# SENSOR.net
KiCad netlist of a schematic drawn in Altium Designer
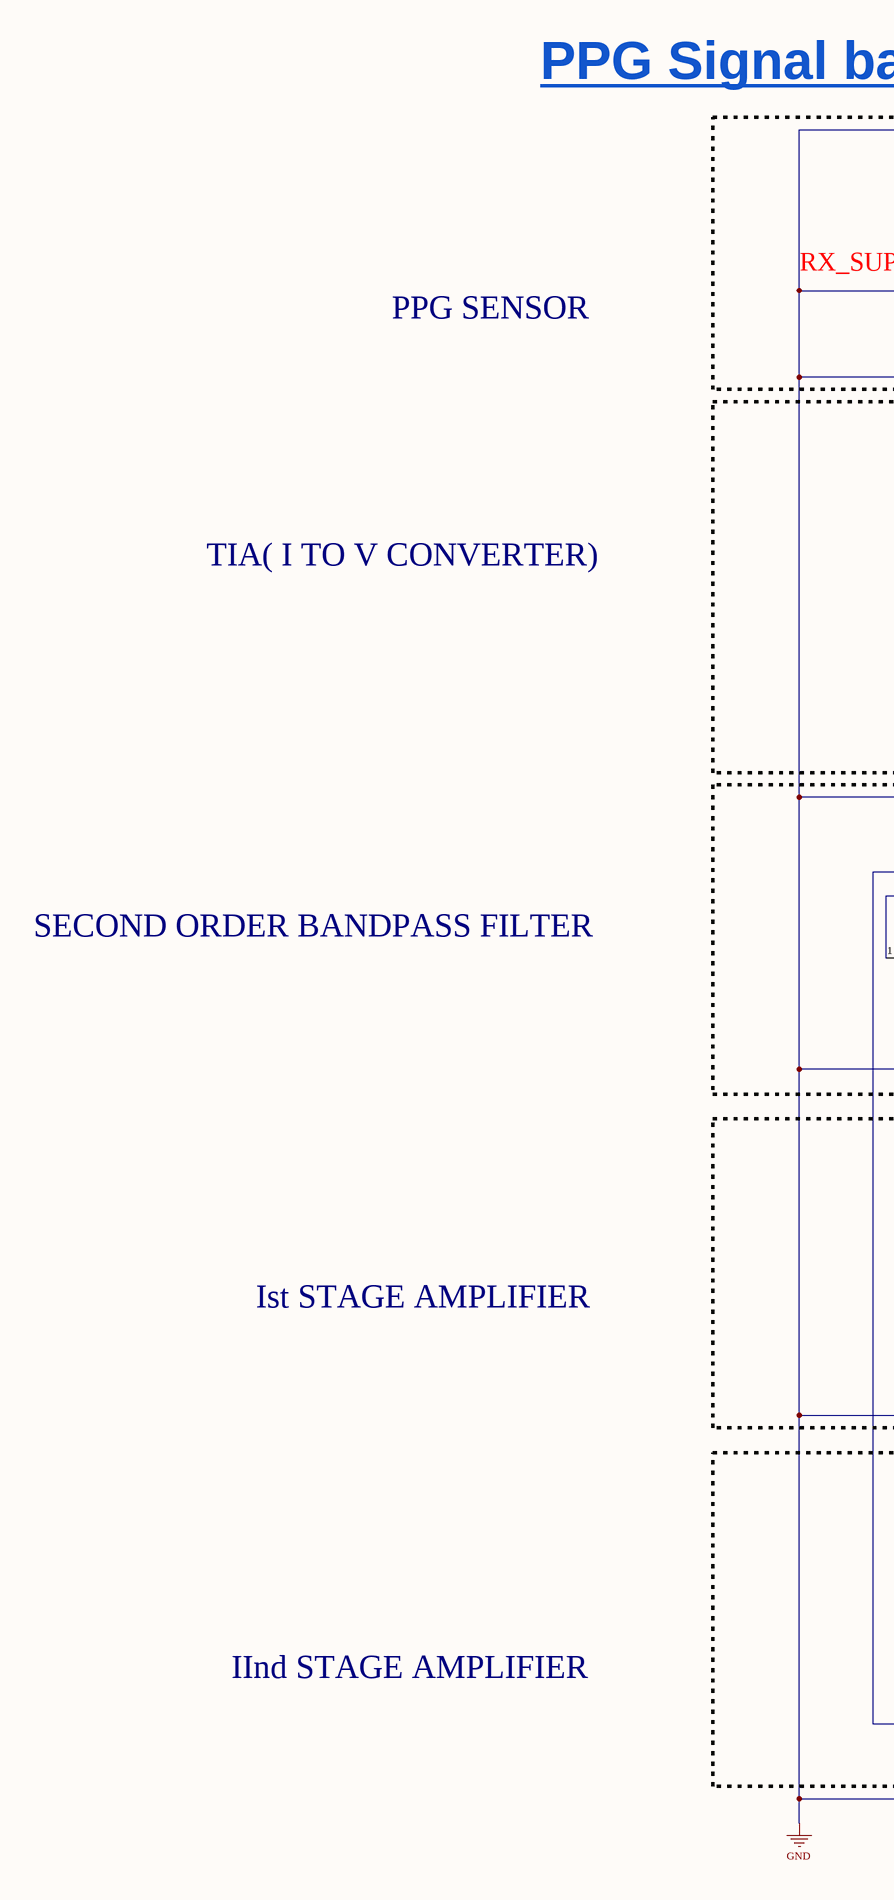
[diagram p0: SENSOR.SchDoc, left]
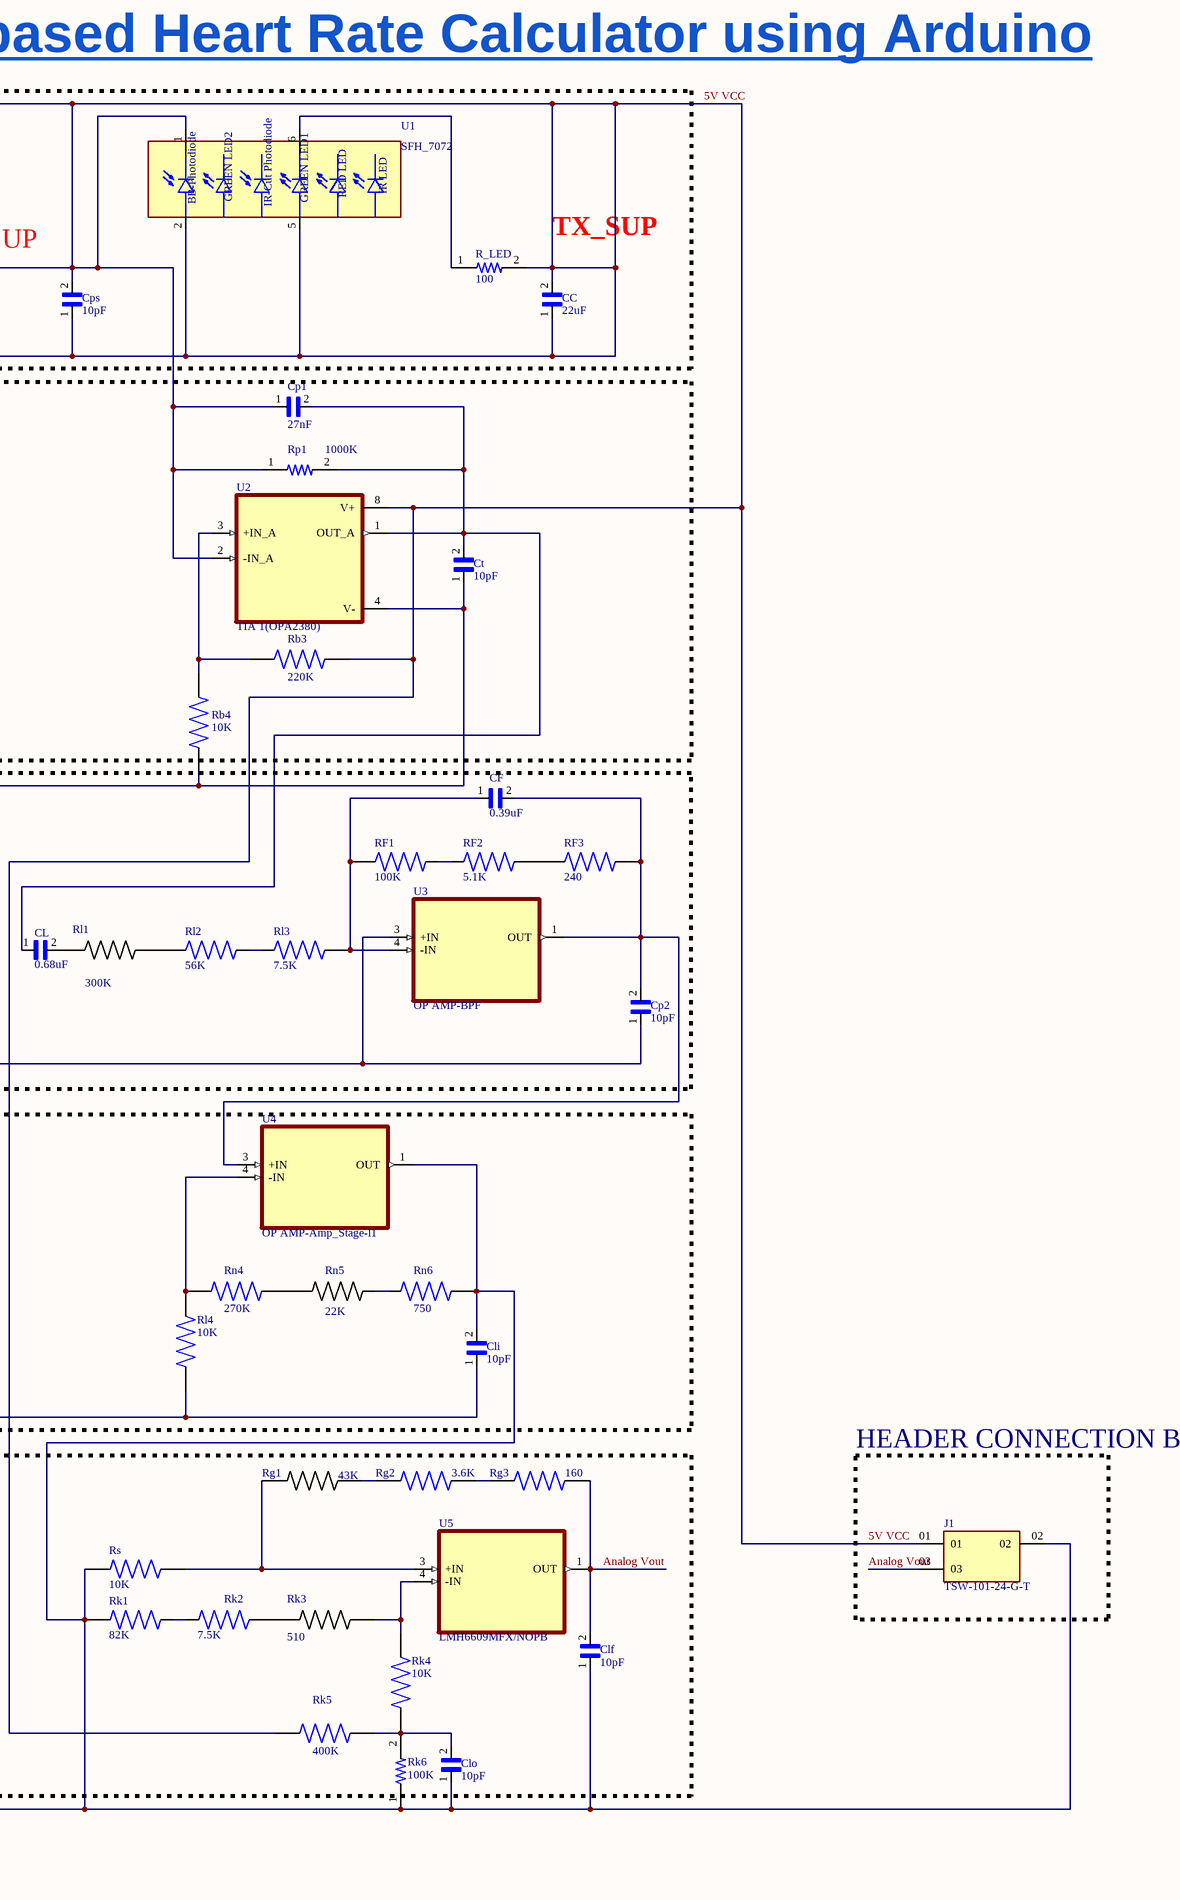
[diagram p1: SENSOR.SchDoc, right]

(export (version "E")
  (design (tool "Eeschema 10.0.6"))
  (components
    (comp (ref "CC")
      (value "22uF")
      (footprint "INDC2112X145N")
      (description "22ÂµF Â±20% 10V Ceramic Capacitor X5R 0805 (2012 Metric)")
      (fields (field (name "MF") "Taiyo Yuden") (field (name "MP") "LMK212BBJ226MG-T"))
      (libsource (lib "LMK212BBJ226MG-T") (part "LMK212BBJ226MG-T"))
    )
    (comp (ref "CF")
      (value "0.39uF")
      (footprint "CAPC2012X140N")
      (description "0.39ÂµF Â±5% 16V Ceramic Capacitor X7R 0805 _2012 Metric_")
      (fields (field (name "MF") "AVX") (field (name "DIGI-KEY_PART_NUMBER") "478-10574-2-ND"))
      (libsource (lib "0805YC394JAT2A") (part "0805YC394JAT2A"))
    )
    (comp (ref "CL")
      (value "0.68uF")
      (footprint "CAPC1608X90N")
      (description "Multilayer Ceramic Capacitor, C Series, 0.68 - F, - 10%, X7R, 16 V, 0603 [1608 Metric]")
      (fields (field (name "MP") "C1608X7R1C684K080AC"))
      (libsource (lib "C1608X7R1C684K080AC") (part "C1608X7R1C684K080AC"))
    )
    (comp (ref "Clf")
      (value "10pF")
      (footprint "CAPC1608X90N")
      (description "10PF 5% 50V C0G 0603")
      (fields (field (name "MP") "06035A100JAT2A"))
      (libsource (lib "06035A100JAT2A") (part "06035A100JAT2A"))
    )
    (comp (ref "Cli")
      (value "10pF")
      (footprint "CAPC1608X90N")
      (description "10PF 5% 50V C0G 0603")
      (fields (field (name "MP") "06035A100JAT2A"))
      (libsource (lib "06035A100JAT2A") (part "06035A100JAT2A"))
    )
    (comp (ref "Clo")
      (value "10pF")
      (footprint "CAPC1608X90N")
      (description "10PF 5% 50V C0G 0603")
      (fields (field (name "MP") "06035A100JAT2A"))
      (libsource (lib "06035A100JAT2A") (part "06035A100JAT2A"))
    )
    (comp (ref "Cp1")
      (value "27nF")
      (footprint "CAPC5750X330N")
      (description "2220GC273KAT1A")
      (fields (field (name "MF") "AVX") (field (name "DIGI-KEY_PART_NUMBER") "478-7018-1-ND"))
      (libsource (lib "06033C104KAT4A") (part "06033C104KAT4A"))
    )
    (comp (ref "Cp2")
      (value "10pF")
      (footprint "CAPC1608X90N")
      (description "10PF 5% 50V C0G 0603")
      (fields (field (name "MP") "06035A100JAT2A"))
      (libsource (lib "06035A100JAT2A") (part "06035A100JAT2A"))
    )
    (comp (ref "Cps")
      (value "10pF")
      (footprint "CAPC1608X90N")
      (description "10PF 5% 50V C0G 0603")
      (fields (field (name "MP") "06035A100JAT2A"))
      (libsource (lib "06035A100JAT2A") (part "06035A100JAT2A"))
    )
    (comp (ref "Ct")
      (value "10pF")
      (footprint "CAPC1608X90N")
      (description "10PF 5% 50V C0G 0603")
      (fields (field (name "MP") "06035A100JAT2A"))
      (libsource (lib "06035A100JAT2A") (part "06035A100JAT2A"))
    )
    (comp (ref "J1")
      (value "TSW-101-24-G-T")
      (footprint "SAMTEC_TSW-101-24-G-T")
      (description "Connector Header Through Hole 3 position")
      (fields (field (name "MF") "Samtec"))
      (libsource (lib "TSW-101-24-G-T") (part "TSW-101-24-G-T"))
    )
    (comp (ref "Rb3")
      (value "220K")
      (footprint "RESC1005X40N")
      (description "Fixed Resistor CRGCQ 0402 220K 1%")
      (fields (field (name "MP") "CRGCQ0402F220K"))
      (libsource (lib "CRGCQ0402F220K") (part "CRGCQ0402F220K"))
    )
    (comp (ref "Rb4")
      (value "10K")
      (footprint "RESC0603X26N")
      (description "10 kOhms Â±1% 0.05W, 1/20W Chip Resistor 0201 (0603 Metric) Thick Film")
      (fields (field (name "MP") "RMCF0201FT10K0") (field (name "MF") "Stackpole Electronics Inc"))
      (libsource (lib "RMCF0201FT10K0") (part "RMCF0201FT10K0"))
    )
    (comp (ref "RF1")
      (value "100K")
      (footprint "RESC1005X40N")
      (description "RES, THIN FILM, 100K, 0.5%, 0.063W, 0402, REEL")
      (fields (field (name "MP") "RR0510P-104-D"))
      (libsource (lib "RR0510P-104-D") (part "RR0510P-104-D"))
    )
    (comp (ref "RF2")
      (value "5.1K")
      (footprint "RES_ERA3AEB512V")
      (description "5.1 kOhms 0.1% 0.1W, 1/10W Chip Resistor 0603 (1608 Metric) Automotive AEC-Q200 Thin Film")
      (fields (field (name "MF") "Panasonic") (field (name "MP") "ERA-3AEB512V"))
      (libsource (lib "ERA3AEB512V") (part "ERA3AEB512V"))
    )
    (comp (ref "RF3")
      (value "240")
      (footprint "RES_ERA2AED241X")
      (description "240 Ohms 0.5% 0.063W, 1/16W Chip Resistor 0402 (1005 Metric) Automotive AEC-Q200 Thin Film")
      (fields (field (name "MF") "Panasonic") (field (name "MP") "ERA-2AED241X"))
      (libsource (lib "ERA2AED241X") (part "ERA2AED241X"))
    )
    (comp (ref "Rg1")
      (value "43K")
      (footprint "*RES_ERJ1GNF4302C")
      (description "None")
      (fields (field (name "MP") "ERJ1GNF4302C") (field (name "MF") "Panasonic"))
      (libsource (lib "ERJ1GNF4302C") (part "ERJ1GNF4302C"))
    )
    (comp (ref "Rg2")
      (value "3.6K")
      (footprint "RESC1005X35N")
      (fields (field (name "MP") "RMCF0402FT3K60"))
      (libsource (lib "RMCF0402FT3K60") (part "RMCF0402FT3K60"))
    )
    (comp (ref "Rg3")
      (value "160")
      (footprint "RESC0603X26N")
      (description "Res Thick Film 0201 160 Ohm 1% 0.05W(1/20W) Â±200ppm/Â°C Pad SMD T/R")
      (fields (field (name "MP") "RC0201FR-07160RL") (field (name "MF") "Yageo"))
      (libsource (lib "RC0201FR-07160RL") (part "RC0201FR-07160RL"))
    )
    (comp (ref "Rk1")
      (value "82K")
      (footprint "RESC1005X40N")
      (description "Fixed Resistor CRGCQ 0402 82K 1%")
      (fields (field (name "MP") "CRGCQ0402F82K"))
      (libsource (lib "CRGCQ0402F82K") (part "CRGCQ0402F82K"))
    )
    (comp (ref "Rk2")
      (value "7.5K")
      (footprint "RESC1508X50N")
      (fields (field (name "MP") "RNCP0603FTD7K50"))
      (libsource (lib "RNCP0603FTD7K50") (part "RNCP0603FTD7K50"))
    )
    (comp (ref "Rk3")
      (value "510")
      (footprint "*RESC0603X26N")
      (libsource (lib "RC0201FR-07510RL") (part "RC0201FR-07510RL"))
    )
    (comp (ref "Rk4")
      (value "10K")
      (footprint "RESC0603X26N")
      (description "10 kOhms Â±1% 0.05W, 1/20W Chip Resistor 0201 (0603 Metric) Thick Film")
      (fields (field (name "MP") "RMCF0201FT10K0") (field (name "MF") "Stackpole Electronics Inc"))
      (libsource (lib "RMCF0201FT10K0") (part "RMCF0201FT10K0"))
    )
    (comp (ref "Rk5")
      (value "400K")
      (footprint "RESC2012X50N")
      (fields (field (name "MP") "CRCW0805400KJNTA"))
      (libsource (lib "CRCW0805400KJNTA") (part "CRCW0805400KJNTA"))
    )
    (comp (ref "Rk6")
      (value "100K")
      (footprint "RESC0603X26N")
      (description "100 kOhms Â±5% 0.05W, 1/20W Chip Resistor 0201 _0603 Metric_ Moisture Resistant Thick Film")
      (fields (field (name "DIGI-KEY_PART_NUMBER") "311-100KNCT-ND") (field (name "MF") "Yageo"))
      (libsource (lib "RC0201JR-07100KL") (part "RC0201JR-07100KL"))
    )
    (comp (ref "Rl1")
      (value "300K")
      (footprint "*RES_ERA3AEB304V")
      (libsource (lib "ERA3AEB304V") (part "ERA3AEB304V"))
    )
    (comp (ref "Rl2")
      (value "56K")
      (footprint "RESC1005X40N")
      (description "Fixed Resistor CRGCQ 0402 56K 1%")
      (fields (field (name "MP") "CRGCQ0402F56K"))
      (libsource (lib "CRGCQ0402F56K") (part "CRGCQ0402F56K"))
    )
    (comp (ref "Rl3")
      (value "7.5K")
      (footprint "RESC1508X50N")
      (fields (field (name "MP") "RNCP0603FTD7K50"))
      (libsource (lib "RNCP0603FTD7K50") (part "RNCP0603FTD7K50"))
    )
    (comp (ref "Rl4")
      (value "10K")
      (footprint "RESC0603X26N")
      (description "10 kOhms Â±1% 0.05W, 1/20W Chip Resistor 0201 (0603 Metric) Thick Film")
      (fields (field (name "MP") "RMCF0201FT10K0") (field (name "MF") "Stackpole Electronics Inc"))
      (libsource (lib "RMCF0201FT10K0") (part "RMCF0201FT10K0"))
    )
    (comp (ref "Rn4")
      (value "270K")
      (footprint "RESC2012X65N")
      (description "CRG0805 1% 270K")
      (fields (field (name "MP") "CRG0805F270K"))
      (libsource (lib "CRG0805F270K") (part "CRG0805F270K"))
    )
    (comp (ref "Rn5")
      (value "22K")
      (footprint "*RES_ERA2AEB223X")
      (libsource (lib "ERA2AEB223X") (part "ERA2AEB223X"))
    )
    (comp (ref "Rn6")
      (value "750")
      (footprint "RES_ERA3AEB751V")
      (description "750 Ohms 0.1% 0.1W, 1/10W Chip Resistor 0603 (1608 Metric) Automotive AEC-Q200 Thin Film")
      (fields (field (name "MP") "ERA-3AEB751V") (field (name "MF") "Panasonic"))
      (libsource (lib "ERA3AEB751V") (part "ERA3AEB751V"))
    )
    (comp (ref "Rp1")
      (value "1000K")
      (footprint "RESC0603X26N")
      (description "1 MOhms Â±1% 0.05W, 1/20W Chip Resistor 0201 (0603 Metric) Moisture Resistant Thick Film")
      (fields (field (name "MP") "RC0201FR-071ML") (field (name "MF") "Yageo"))
      (libsource (lib "RC0201FR-071ML") (part "RC0201FR-071ML"))
    )
    (comp (ref "Rs")
      (value "10K")
      (footprint "RESC0603X26N")
      (description "10 kOhms Â±1% 0.05W, 1/20W Chip Resistor 0201 (0603 Metric) Thick Film")
      (fields (field (name "MP") "RMCF0201FT10K0") (field (name "MF") "Stackpole Electronics Inc"))
      (libsource (lib "RMCF0201FT10K0") (part "RMCF0201FT10K0"))
    )
    (comp (ref "R_LED")
      (value "100")
      (footprint "RESC0603X26N")
      (description "100 Ohms Â±1% 0.05W, 1/20W Chip Resistor 0201 _0603 Metric_ Moisture Resistant Thick Film")
      (fields (field (name "MF") "Yageo") (field (name "MP") "RC0201FR-07100RL"))
      (libsource (lib "RC0201FR-07100RL") (part "RC0201FR-07100RL"))
    )
    (comp (ref "U1")
      (value "SFH_7072")
      (footprint "XDCR_SFH_7072")
      (description "Reflective Optical Sensor 6-SMD, No Lead")
      (fields (field (name "MP") "SFH 7072") (field (name "MF") "OSRAM Opto"))
      (libsource (lib "SFH_7072") (part "SFH_7072"))
    )
    (comp (ref "U2")
      (value "TIA 1(OPA2380)")
      (footprint "SOP65P490X110-8N")
      (fields (field (name "MP") "OPA2380AIDGKT"))
      (libsource (lib "OPA2380AIDGKT") (part "OPA2380AIDGKT"))
    )
    (comp (ref "U3")
      (value "OP AMP-BPF")
      (footprint "SOT95P280X145-5N")
      (fields (field (name "MP") "LMH6609MFX/NOPB"))
      (libsource (lib "LMH6609MFX_NOPB") (part "LMH6609MFX/NOPB"))
    )
    (comp (ref "U4")
      (value "OP AMP-Amp_Stage-l1")
      (footprint "SOT95P280X145-5N")
      (fields (field (name "MP") "LMH6609MFX/NOPB"))
      (libsource (lib "LMH6609MFX_NOPB") (part "LMH6609MFX/NOPB"))
    )
    (comp (ref "U5")
      (value "LMH6609MFX/NOPB")
      (footprint "SOT95P280X145-5N")
      (libsource (lib "LMH6609MFX_NOPB") (part "LMH6609MFX/NOPB"))
    )
  )
  (nets
    (net (code "1") (name "/Analog Vout") (class "Default")
      (node (ref "Clf") (pin "2") (pinfunction "2_2") (pintype "passive"))
      (node (ref "J1") (pin "03") (pinfunction "03_03") (pintype "passive"))
      (node (ref "Rg3") (pin "2") (pinfunction "2_2") (pintype "passive"))
      (node (ref "U5") (pin "1") (pinfunction "OUT_1") (pintype "output"))
    )
    (net (code "2") (name "GND") (class "Default")
      (node (ref "CC") (pin "1") (pinfunction "1_1") (pintype "passive"))
      (node (ref "CC") (pin "2") (pinfunction "2_2") (pintype "passive"))
      (node (ref "Clf") (pin "1") (pinfunction "1_1") (pintype "passive"))
      (node (ref "Cli") (pin "1") (pinfunction "1_1") (pintype "passive"))
      (node (ref "Cli") (pin "2") (pinfunction "2_2") (pintype "passive"))
      (node (ref "Clo") (pin "1") (pinfunction "1_1") (pintype "passive"))
      (node (ref "Cp1") (pin "1") (pinfunction "1_1") (pintype "passive"))
      (node (ref "Cp2") (pin "1") (pinfunction "1_1") (pintype "passive"))
      (node (ref "Cps") (pin "1") (pinfunction "1_1") (pintype "passive"))
      (node (ref "Cps") (pin "2") (pinfunction "2_2") (pintype "passive"))
      (node (ref "Ct") (pin "1") (pinfunction "1_1") (pintype "passive"))
      (node (ref "J1") (pin "01") (pinfunction "01_01") (pintype "passive"))
      (node (ref "J1") (pin "02") (pinfunction "02_02") (pintype "passive"))
      (node (ref "R_LED") (pin "2") (pinfunction "2_2") (pintype "passive"))
      (node (ref "Rb3") (pin "2") (pinfunction "2_2") (pintype "passive"))
      (node (ref "Rb4") (pin "1") (pinfunction "1_1") (pintype "passive"))
      (node (ref "Rk1") (pin "1") (pinfunction "1_1") (pintype "passive"))
      (node (ref "Rk5") (pin "1") (pinfunction "1_1") (pintype "passive"))
      (node (ref "Rk6") (pin "1") (pinfunction "1_1") (pintype "passive"))
      (node (ref "Rl4") (pin "1") (pinfunction "1_1") (pintype "passive"))
      (node (ref "Rn6") (pin "2") (pinfunction "2_2") (pintype "passive"))
      (node (ref "Rp1") (pin "1") (pinfunction "1_1") (pintype "passive"))
      (node (ref "Rs") (pin "1") (pinfunction "1_1") (pintype "passive"))
      (node (ref "U1") (pin "1") (pinfunction "BPC_1") (pintype "passive"))
      (node (ref "U1") (pin "2") (pinfunction "BPA_2") (pintype "passive"))
      (node (ref "U1") (pin "5") (pinfunction "G1A_5") (pintype "passive"))
      (node (ref "U2") (pin "2") (pinfunction "-IN_A_2") (pintype "input"))
      (node (ref "U2") (pin "4") (pinfunction "V-_4") (pintype "power_in"))
      (node (ref "U2") (pin "8") (pinfunction "V+_8") (pintype "power_in"))
      (node (ref "U3") (pin "3") (pinfunction "+IN_3") (pintype "input"))
      (node (ref "U4") (pin "1") (pinfunction "OUT_1") (pintype "output"))
    )
    (net (code "3") (name "Net-(CL-Pad2)") (class "Default")
      (node (ref "CL") (pin "2") (pinfunction "2_2") (pintype "passive"))
      (node (ref "Rl1") (pin "1") (pinfunction "1_1") (pintype "passive"))
    )
    (net (code "4") (name "Net-(Clo-Pad2)") (class "Default")
      (node (ref "Clo") (pin "2") (pinfunction "2_2") (pintype "passive"))
      (node (ref "Rk4") (pin "1") (pinfunction "1_1") (pintype "passive"))
      (node (ref "Rk5") (pin "2") (pinfunction "2_2") (pintype "passive"))
      (node (ref "Rk6") (pin "2") (pinfunction "2_2") (pintype "passive"))
    )
    (net (code "5") (name "Net-(RF1-Pad2)") (class "Default")
      (node (ref "RF1") (pin "2") (pinfunction "2_2") (pintype "passive"))
      (node (ref "RF2") (pin "1") (pinfunction "1_1") (pintype "passive"))
    )
    (net (code "6") (name "Net-(RF2-Pad2)") (class "Default")
      (node (ref "RF2") (pin "2") (pinfunction "2_2") (pintype "passive"))
      (node (ref "RF3") (pin "1") (pinfunction "1_1") (pintype "passive"))
    )
    (net (code "7") (name "Net-(Rg1-Pad2)") (class "Default")
      (node (ref "Rg1") (pin "2") (pinfunction "2_2") (pintype "passive"))
      (node (ref "Rg2") (pin "1") (pinfunction "1_1") (pintype "passive"))
    )
    (net (code "8") (name "Net-(Rg2-Pad2)") (class "Default")
      (node (ref "Rg2") (pin "2") (pinfunction "2_2") (pintype "passive"))
      (node (ref "Rg3") (pin "1") (pinfunction "1_1") (pintype "passive"))
    )
    (net (code "9") (name "Net-(Rk1-Pad2)") (class "Default")
      (node (ref "Rk1") (pin "2") (pinfunction "2_2") (pintype "passive"))
      (node (ref "Rk2") (pin "1") (pinfunction "1_1") (pintype "passive"))
    )
    (net (code "10") (name "Net-(Rk2-Pad2)") (class "Default")
      (node (ref "Rk2") (pin "2") (pinfunction "2_2") (pintype "passive"))
      (node (ref "Rk3") (pin "1") (pinfunction "1_1") (pintype "passive"))
    )
    (net (code "11") (name "Net-(Rl1-Pad2)") (class "Default")
      (node (ref "Rl1") (pin "2") (pinfunction "2_2") (pintype "passive"))
      (node (ref "Rl2") (pin "1") (pinfunction "1_1") (pintype "passive"))
    )
    (net (code "12") (name "Net-(Rl2-Pad2)") (class "Default")
      (node (ref "Rl2") (pin "2") (pinfunction "2_2") (pintype "passive"))
      (node (ref "Rl3") (pin "1") (pinfunction "1_1") (pintype "passive"))
    )
    (net (code "13") (name "Net-(Rn4-Pad2)") (class "Default")
      (node (ref "Rn4") (pin "2") (pinfunction "2_2") (pintype "passive"))
      (node (ref "Rn5") (pin "1") (pinfunction "1_1") (pintype "passive"))
    )
    (net (code "14") (name "Net-(Rn5-Pad2)") (class "Default")
      (node (ref "Rn5") (pin "2") (pinfunction "2_2") (pintype "passive"))
      (node (ref "Rn6") (pin "1") (pinfunction "1_1") (pintype "passive"))
    )
    (net (code "15") (name "Net-(U1-G1C)") (class "Default")
      (node (ref "R_LED") (pin "1") (pinfunction "1_1") (pintype "passive"))
      (node (ref "U1") (pin "6") (pinfunction "G1C_6") (pintype "passive"))
    )
    (net (code "16") (name "Net-(U2-+IN_A)") (class "Default")
      (node (ref "Rb3") (pin "1") (pinfunction "1_1") (pintype "passive"))
      (node (ref "Rb4") (pin "2") (pinfunction "2_2") (pintype "passive"))
      (node (ref "U2") (pin "3") (pinfunction "+IN_A_3") (pintype "input"))
    )
    (net (code "17") (name "Net-(U2-OUT_A)") (class "Default")
      (node (ref "CL") (pin "1") (pinfunction "1_1") (pintype "passive"))
      (node (ref "Cp1") (pin "2") (pinfunction "2_2") (pintype "passive"))
      (node (ref "Ct") (pin "2") (pinfunction "2_2") (pintype "passive"))
      (node (ref "Rp1") (pin "2") (pinfunction "2_2") (pintype "passive"))
      (node (ref "U2") (pin "1") (pinfunction "OUT_A_1") (pintype "output"))
    )
    (net (code "18") (name "Net-(U3--IN)") (class "Default")
      (node (ref "CF") (pin "1") (pinfunction "1_1") (pintype "passive"))
      (node (ref "RF1") (pin "1") (pinfunction "1_1") (pintype "passive"))
      (node (ref "Rl3") (pin "2") (pinfunction "2_2") (pintype "passive"))
      (node (ref "U3") (pin "4") (pinfunction "-IN_4") (pintype "input"))
    )
    (net (code "19") (name "Net-(U3-OUT)") (class "Default")
      (node (ref "CF") (pin "2") (pinfunction "2_2") (pintype "passive"))
      (node (ref "Cp2") (pin "2") (pinfunction "2_2") (pintype "passive"))
      (node (ref "RF3") (pin "2") (pinfunction "2_2") (pintype "passive"))
      (node (ref "U3") (pin "1") (pinfunction "OUT_1") (pintype "output"))
      (node (ref "U4") (pin "3") (pinfunction "+IN_3") (pintype "input"))
    )
    (net (code "20") (name "Net-(U4--IN)") (class "Default")
      (node (ref "Rl4") (pin "2") (pinfunction "2_2") (pintype "passive"))
      (node (ref "Rn4") (pin "1") (pinfunction "1_1") (pintype "passive"))
      (node (ref "U4") (pin "4") (pinfunction "-IN_4") (pintype "input"))
    )
    (net (code "21") (name "Net-(U5-+IN)") (class "Default")
      (node (ref "Rg1") (pin "1") (pinfunction "1_1") (pintype "passive"))
      (node (ref "Rs") (pin "2") (pinfunction "2_2") (pintype "passive"))
      (node (ref "U5") (pin "3") (pinfunction "+IN_3") (pintype "input"))
    )
    (net (code "22") (name "Net-(U5--IN)") (class "Default")
      (node (ref "Rk3") (pin "2") (pinfunction "2_2") (pintype "passive"))
      (node (ref "Rk4") (pin "2") (pinfunction "2_2") (pintype "passive"))
      (node (ref "U5") (pin "4") (pinfunction "-IN_4") (pintype "input"))
    )
  )
)
